# durtest4.net
KiCad netlist of a schematic drawn in EAGLE
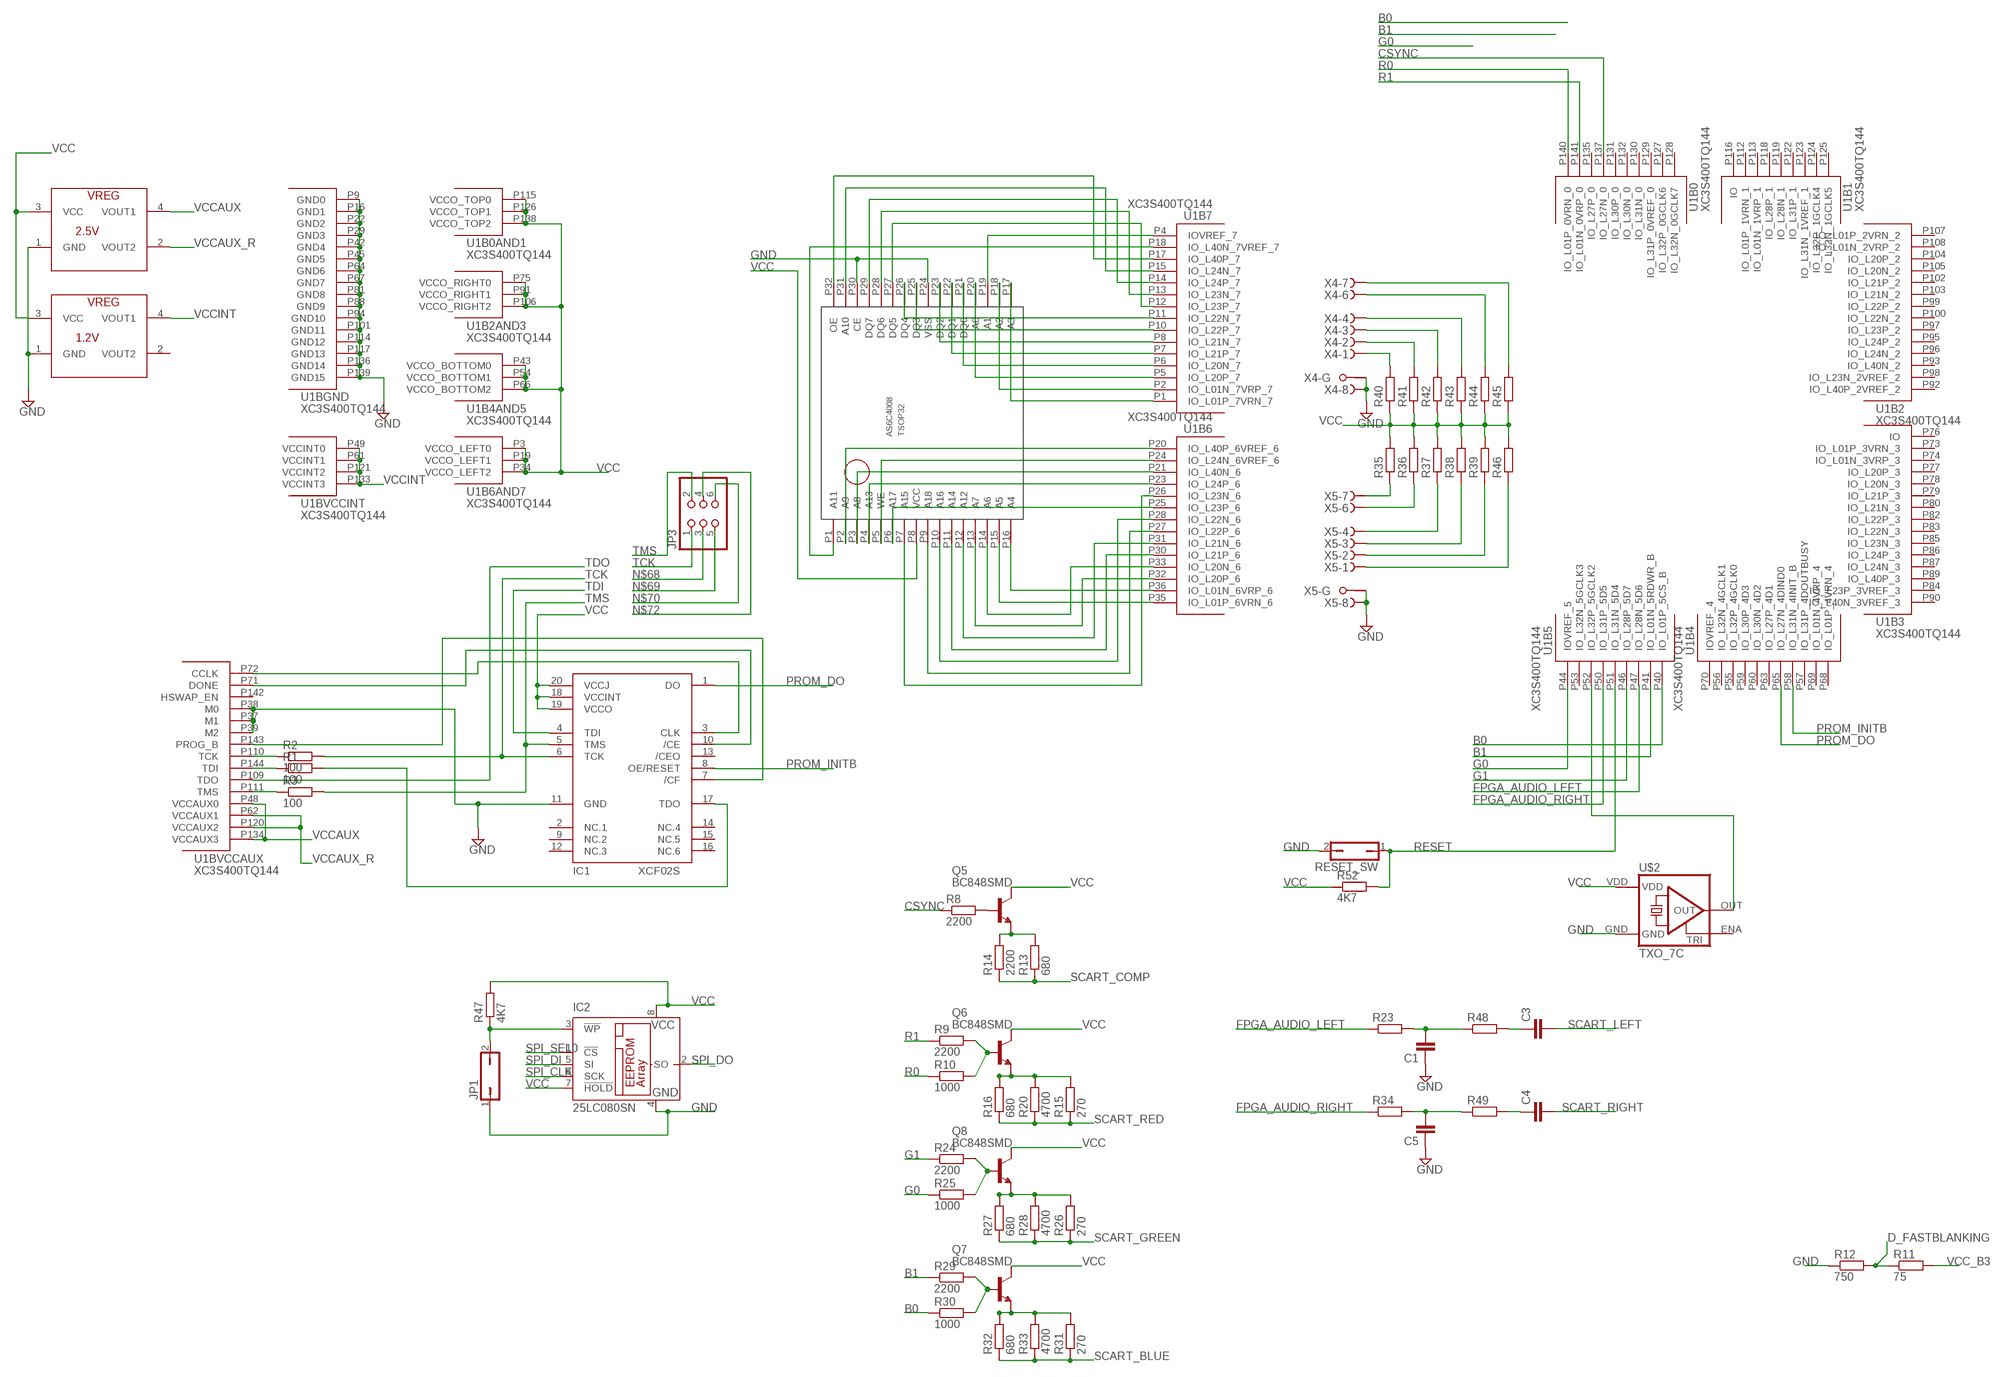
[diagram p0: schematic, sheet 1, part 1 of 2]
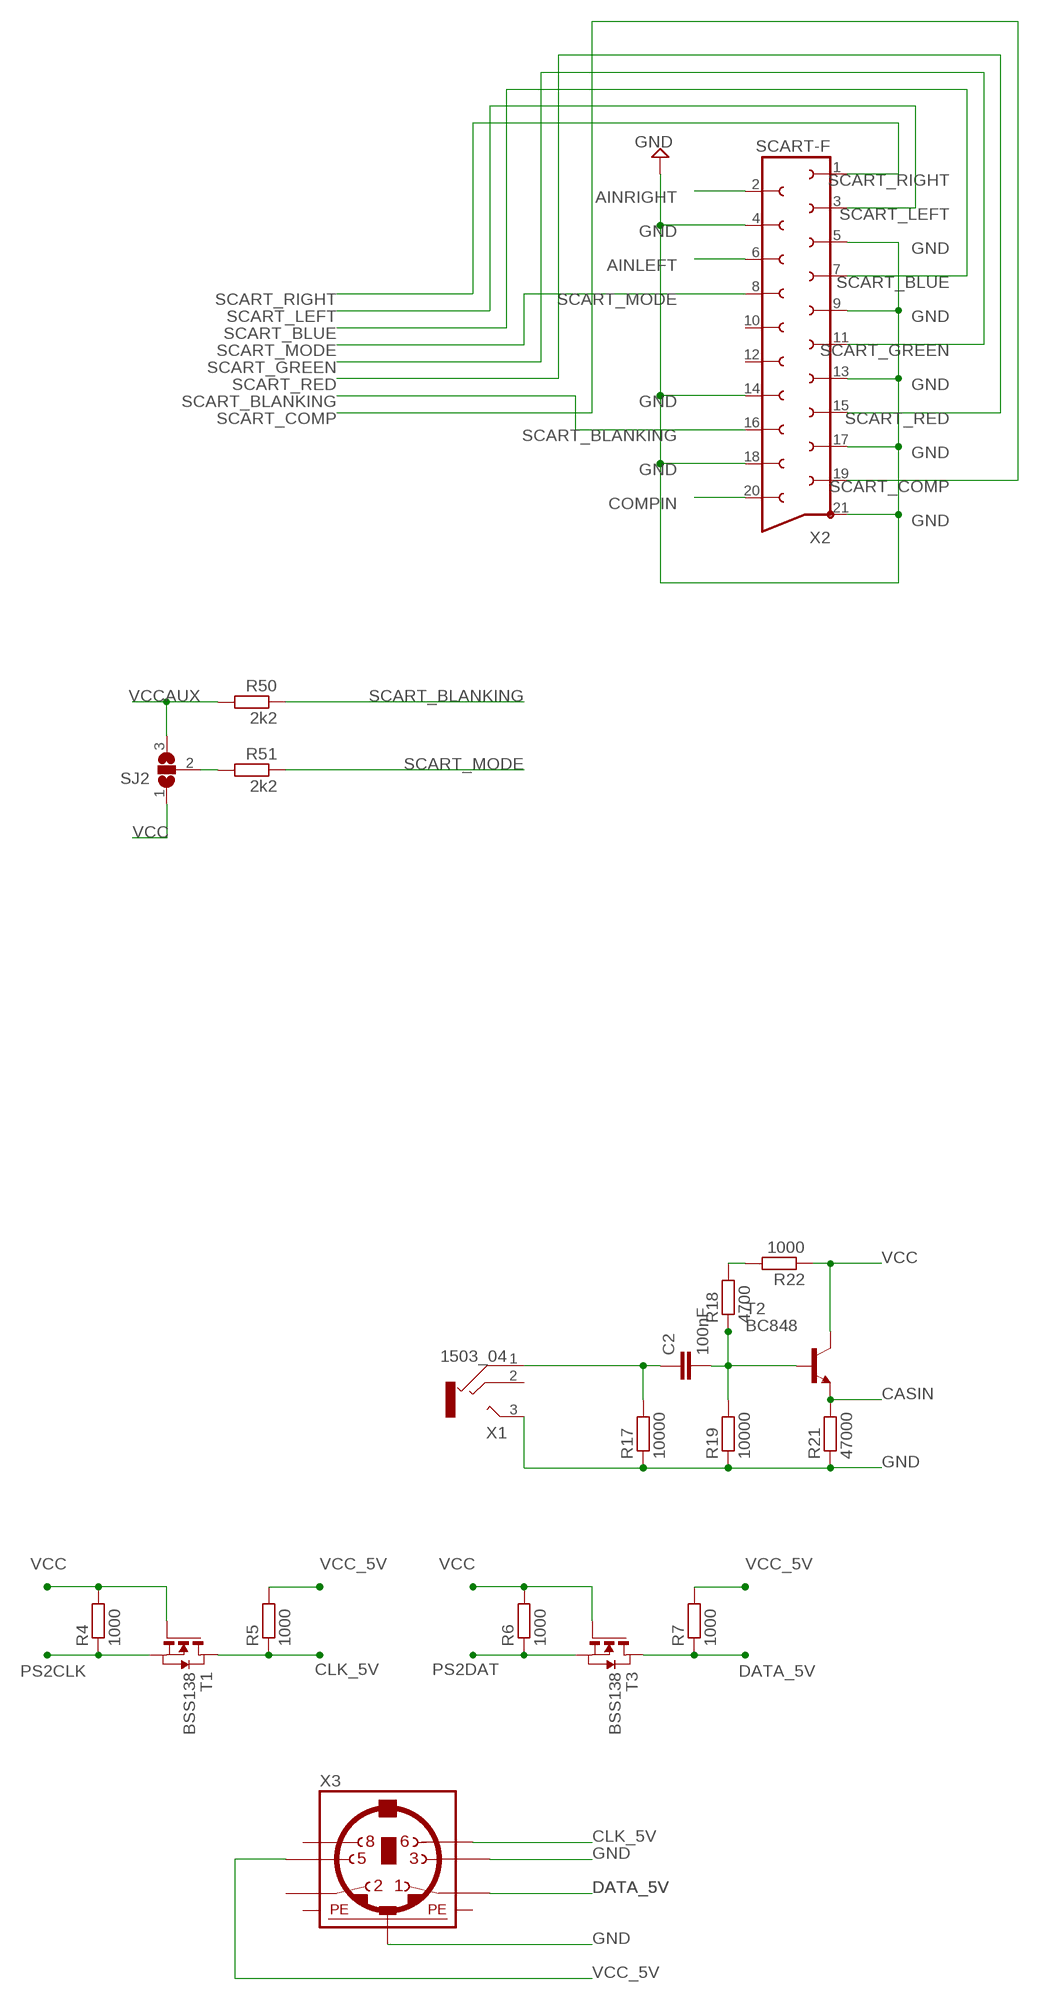
[diagram p1: schematic, sheet 1, part 2 of 2]

(export (version "E")
  (design (tool "Eeschema 10.0.6"))
  (components
    (comp (ref "C1")
      (value "C-EUC0603")
      (footprint "eagle-import:C0603")
      (libsource (lib "eagle-import") (part "C-EUC0603"))
    )
    (comp (ref "C2")
      (value "100nF")
      (footprint "eagle-import:C0603")
      (libsource (lib "eagle-import") (part "C-EUC0603"))
    )
    (comp (ref "C3")
      (value "C-EUC0603")
      (footprint "eagle-import:C0603")
      (libsource (lib "eagle-import") (part "C-EUC0603"))
    )
    (comp (ref "C4")
      (value "C-EUC0603")
      (footprint "eagle-import:C0603")
      (libsource (lib "eagle-import") (part "C-EUC0603"))
    )
    (comp (ref "C5")
      (value "C-EUC0603")
      (footprint "eagle-import:C0603")
      (libsource (lib "eagle-import") (part "C-EUC0603"))
    )
    (comp (ref "IC1")
      (value "XCF02S")
      (footprint "eagle-import:VO20")
      (libsource (lib "eagle-import") (part "XCF02S"))
    )
    (comp (ref "IC2")
      (value "25LC080SN")
      (footprint "eagle-import:SO-08")
      (fields (field (name "MF") "MICROCHIP") (field (name "MPN") "25LC080/SN"))
      (libsource (lib "eagle-import") (part "25SNLC080"))
    )
    (comp (ref "JP1")
      (value "JP1Q")
      (footprint "eagle-import:JP1")
      (libsource (lib "eagle-import") (part "JP1Q"))
    )
    (comp (ref "JP3")
      (value "PINHD-2X3")
      (footprint "eagle-import:2X03")
      (libsource (lib "eagle-import") (part "PINHD-2X3"))
    )
    (comp (ref "Q5")
      (value "BC848SMD")
      (footprint "eagle-import:SOT23")
      (libsource (lib "eagle-import") (part "BC848SMD"))
    )
    (comp (ref "Q6")
      (value "BC848SMD")
      (footprint "eagle-import:SOT23")
      (libsource (lib "eagle-import") (part "BC848SMD"))
    )
    (comp (ref "Q7")
      (value "BC848SMD")
      (footprint "eagle-import:SOT23")
      (libsource (lib "eagle-import") (part "BC848SMD"))
    )
    (comp (ref "Q8")
      (value "BC848SMD")
      (footprint "eagle-import:SOT23")
      (libsource (lib "eagle-import") (part "BC848SMD"))
    )
    (comp (ref "R1")
      (value "100")
      (footprint "eagle-import:R0805")
      (libsource (lib "eagle-import") (part "R-EU_R0805"))
    )
    (comp (ref "R2")
      (value "100")
      (footprint "eagle-import:R0805")
      (libsource (lib "eagle-import") (part "R-EU_R0805"))
    )
    (comp (ref "R3")
      (value "100")
      (footprint "eagle-import:R0805")
      (libsource (lib "eagle-import") (part "R-EU_R0805"))
    )
    (comp (ref "R4")
      (value "1000")
      (footprint "eagle-import:R0805")
      (libsource (lib "eagle-import") (part "R-EU_R0805"))
    )
    (comp (ref "R5")
      (value "1000")
      (footprint "eagle-import:R0805")
      (libsource (lib "eagle-import") (part "R-EU_R0805"))
    )
    (comp (ref "R6")
      (value "1000")
      (footprint "eagle-import:R0805")
      (libsource (lib "eagle-import") (part "R-EU_R0805"))
    )
    (comp (ref "R7")
      (value "1000")
      (footprint "eagle-import:R0805")
      (libsource (lib "eagle-import") (part "R-EU_R0805"))
    )
    (comp (ref "R8")
      (value "2200")
      (footprint "eagle-import:R0805")
      (libsource (lib "eagle-import") (part "R-EU_R0805"))
    )
    (comp (ref "R9")
      (value "2200")
      (footprint "eagle-import:R0805")
      (libsource (lib "eagle-import") (part "R-EU_R0805"))
    )
    (comp (ref "R10")
      (value "1000")
      (footprint "eagle-import:R0805")
      (libsource (lib "eagle-import") (part "R-EU_R0805"))
    )
    (comp (ref "R11")
      (value "75")
      (footprint "eagle-import:R0805")
      (libsource (lib "eagle-import") (part "R-EU_R0805"))
    )
    (comp (ref "R12")
      (value "750")
      (footprint "eagle-import:R0805")
      (libsource (lib "eagle-import") (part "R-EU_R0805"))
    )
    (comp (ref "R13")
      (value "680")
      (footprint "eagle-import:R0805")
      (libsource (lib "eagle-import") (part "R-EU_R0805"))
    )
    (comp (ref "R14")
      (value "2200")
      (footprint "eagle-import:R0805")
      (libsource (lib "eagle-import") (part "R-EU_R0805"))
    )
    (comp (ref "R15")
      (value "270")
      (footprint "eagle-import:R0805")
      (libsource (lib "eagle-import") (part "R-EU_R0805"))
    )
    (comp (ref "R16")
      (value "680")
      (footprint "eagle-import:R0805")
      (libsource (lib "eagle-import") (part "R-EU_R0805"))
    )
    (comp (ref "R17")
      (value "10000")
      (footprint "eagle-import:R0805")
      (libsource (lib "eagle-import") (part "R-EU_R0805"))
    )
    (comp (ref "R18")
      (value "4700")
      (footprint "eagle-import:R0805")
      (libsource (lib "eagle-import") (part "R-EU_R0805"))
    )
    (comp (ref "R19")
      (value "10000")
      (footprint "eagle-import:R0805")
      (libsource (lib "eagle-import") (part "R-EU_R0805"))
    )
    (comp (ref "R20")
      (value "4700")
      (footprint "eagle-import:R0805")
      (libsource (lib "eagle-import") (part "R-EU_R0805"))
    )
    (comp (ref "R21")
      (value "47000")
      (footprint "eagle-import:R0805")
      (libsource (lib "eagle-import") (part "R-EU_R0805"))
    )
    (comp (ref "R22")
      (value "1000")
      (footprint "eagle-import:R0805")
      (libsource (lib "eagle-import") (part "R-EU_R0805"))
    )
    (comp (ref "R23")
      (value "R-EU_M0805")
      (footprint "eagle-import:M0805")
      (libsource (lib "eagle-import") (part "resistor_R-EU_M0805"))
    )
    (comp (ref "R24")
      (value "2200")
      (footprint "eagle-import:R0805")
      (libsource (lib "eagle-import") (part "R-EU_R0805"))
    )
    (comp (ref "R25")
      (value "1000")
      (footprint "eagle-import:R0805")
      (libsource (lib "eagle-import") (part "R-EU_R0805"))
    )
    (comp (ref "R26")
      (value "270")
      (footprint "eagle-import:R0805")
      (libsource (lib "eagle-import") (part "R-EU_R0805"))
    )
    (comp (ref "R27")
      (value "680")
      (footprint "eagle-import:R0805")
      (libsource (lib "eagle-import") (part "R-EU_R0805"))
    )
    (comp (ref "R28")
      (value "4700")
      (footprint "eagle-import:R0805")
      (libsource (lib "eagle-import") (part "R-EU_R0805"))
    )
    (comp (ref "R29")
      (value "2200")
      (footprint "eagle-import:R0805")
      (libsource (lib "eagle-import") (part "R-EU_R0805"))
    )
    (comp (ref "R30")
      (value "1000")
      (footprint "eagle-import:R0805")
      (libsource (lib "eagle-import") (part "R-EU_R0805"))
    )
    (comp (ref "R31")
      (value "270")
      (footprint "eagle-import:R0805")
      (libsource (lib "eagle-import") (part "R-EU_R0805"))
    )
    (comp (ref "R32")
      (value "680")
      (footprint "eagle-import:R0805")
      (libsource (lib "eagle-import") (part "R-EU_R0805"))
    )
    (comp (ref "R33")
      (value "4700")
      (footprint "eagle-import:R0805")
      (libsource (lib "eagle-import") (part "R-EU_R0805"))
    )
    (comp (ref "R34")
      (value "R-EU_M0805")
      (footprint "eagle-import:M0805")
      (libsource (lib "eagle-import") (part "resistor_R-EU_M0805"))
    )
    (comp (ref "R35")
      (value "R-EU_M0805")
      (footprint "eagle-import:M0805")
      (libsource (lib "eagle-import") (part "resistor_R-EU_M0805"))
    )
    (comp (ref "R36")
      (value "R-EU_M0805")
      (footprint "eagle-import:M0805")
      (libsource (lib "eagle-import") (part "resistor_R-EU_M0805"))
    )
    (comp (ref "R37")
      (value "R-EU_M0805")
      (footprint "eagle-import:M0805")
      (libsource (lib "eagle-import") (part "resistor_R-EU_M0805"))
    )
    (comp (ref "R38")
      (value "R-EU_M0805")
      (footprint "eagle-import:M0805")
      (libsource (lib "eagle-import") (part "resistor_R-EU_M0805"))
    )
    (comp (ref "R39")
      (value "R-EU_M0805")
      (footprint "eagle-import:M0805")
      (libsource (lib "eagle-import") (part "resistor_R-EU_M0805"))
    )
    (comp (ref "R40")
      (value "R-EU_M0805")
      (footprint "eagle-import:M0805")
      (libsource (lib "eagle-import") (part "resistor_R-EU_M0805"))
    )
    (comp (ref "R41")
      (value "R-EU_M0805")
      (footprint "eagle-import:M0805")
      (libsource (lib "eagle-import") (part "resistor_R-EU_M0805"))
    )
    (comp (ref "R42")
      (value "R-EU_M0805")
      (footprint "eagle-import:M0805")
      (libsource (lib "eagle-import") (part "resistor_R-EU_M0805"))
    )
    (comp (ref "R43")
      (value "R-EU_M0805")
      (footprint "eagle-import:M0805")
      (libsource (lib "eagle-import") (part "resistor_R-EU_M0805"))
    )
    (comp (ref "R44")
      (value "R-EU_M0805")
      (footprint "eagle-import:M0805")
      (libsource (lib "eagle-import") (part "resistor_R-EU_M0805"))
    )
    (comp (ref "R45")
      (value "R-EU_M0805")
      (footprint "eagle-import:M0805")
      (libsource (lib "eagle-import") (part "resistor_R-EU_M0805"))
    )
    (comp (ref "R46")
      (value "R-EU_M0805")
      (footprint "eagle-import:M0805")
      (libsource (lib "eagle-import") (part "resistor_R-EU_M0805"))
    )
    (comp (ref "R47")
      (value "4K7")
      (footprint "eagle-import:R0805")
      (libsource (lib "eagle-import") (part "R-EU_R0805"))
    )
    (comp (ref "R48")
      (value "R-EU_M0805")
      (footprint "eagle-import:M0805")
      (libsource (lib "eagle-import") (part "resistor_R-EU_M0805"))
    )
    (comp (ref "R49")
      (value "R-EU_M0805")
      (footprint "eagle-import:M0805")
      (libsource (lib "eagle-import") (part "resistor_R-EU_M0805"))
    )
    (comp (ref "R50")
      (value "2k2")
      (footprint "eagle-import:M0805")
      (libsource (lib "eagle-import") (part "resistor_R-EU_M0805"))
    )
    (comp (ref "R51")
      (value "2k2")
      (footprint "eagle-import:M0805")
      (libsource (lib "eagle-import") (part "resistor_R-EU_M0805"))
    )
    (comp (ref "R52")
      (value "4K7")
      (footprint "eagle-import:M0805")
      (libsource (lib "eagle-import") (part "resistor_R-EU_M0805"))
    )
    (comp (ref "REG1.2")
      (value "1.2V")
      (footprint "eagle-import:SOT223")
      (libsource (lib "eagle-import") (part "NX1117"))
    )
    (comp (ref "REG2.5")
      (value "2.5V")
      (footprint "eagle-import:SOT223")
      (libsource (lib "eagle-import") (part "NX1117"))
    )
    (comp (ref "RESET_SW")
      (value "JP1Q")
      (footprint "eagle-import:JP1")
      (libsource (lib "eagle-import") (part "JP1Q"))
    )
    (comp (ref "SJ2")
      (value "SJ2W")
      (footprint "eagle-import:SJ_2")
      (libsource (lib "eagle-import") (part "SJ2W"))
    )
    (comp (ref "T1")
      (value "BSS138")
      (footprint "eagle-import:SOT-23")
      (libsource (lib "eagle-import") (part "NMOSSOT23"))
    )
    (comp (ref "T2")
      (value "BC848")
      (footprint "eagle-import:SOT23")
      (libsource (lib "eagle-import") (part "BC848"))
    )
    (comp (ref "T3")
      (value "BSS138")
      (footprint "eagle-import:SOT-23")
      (libsource (lib "eagle-import") (part "NMOSSOT23"))
    )
    (comp (ref "U$1")
      (value "AS6C4008")
      (footprint "eagle-import:TSOP32")
      (libsource (lib "eagle-import") (part "AS6C4008"))
    )
    (comp (ref "U$2")
      (value "TXO_7C")
      (footprint "eagle-import:OSC_7C")
      (libsource (lib "eagle-import") (part "TXO_7C"))
    )
    (comp (ref "U1")
      (value "XC3S400TQ144")
      (footprint "eagle-import:TQ144")
      (libsource (lib "eagle-import") (part "XC3S400TQ144"))
    )
    (comp (ref "X1")
      (value "1503_04")
      (footprint "eagle-import:1503_04")
      (libsource (lib "eagle-import") (part "1503_04"))
    )
    (comp (ref "X2")
      (value "SCART-F")
      (footprint "eagle-import:SCART-F")
      (libsource (lib "eagle-import") (part "SCART-F"))
    )
    (comp (ref "X3")
      (value "MINI_DIN_6")
      (footprint "eagle-import:M_DIN6")
      (libsource (lib "eagle-import") (part "MINI_DIN_6"))
    )
    (comp (ref "X4")
      (value "F09HPS")
      (footprint "eagle-import:F09HP")
      (libsource (lib "eagle-import") (part "F09HPS"))
    )
    (comp (ref "X5")
      (value "F09HPS")
      (footprint "eagle-import:F09HP")
      (libsource (lib "eagle-import") (part "F09HPS"))
    )
  )
  (nets
    (net (code "1") (name "/AINLEFT") (class "Default")
      (node (ref "X2") (pin "6") (pinfunction "6_6") (pintype "passive"))
    )
    (net (code "2") (name "/AINRIGHT") (class "Default")
      (node (ref "X2") (pin "2") (pinfunction "2_2") (pintype "passive"))
    )
    (net (code "3") (name "/B0") (class "Default")
      (node (ref "R30") (pin "1") (pinfunction "1_1") (pintype "passive"))
      (node (ref "U1") (pin "P40") (pinfunction "IO_L01P_5CS_B_P40") (pintype "bidirectional"))
    )
    (net (code "4") (name "/B1") (class "Default")
      (node (ref "R29") (pin "1") (pinfunction "1_1") (pintype "passive"))
      (node (ref "U1") (pin "P41") (pinfunction "IO_L01N_5RDWR_B_P41") (pintype "bidirectional"))
    )
    (net (code "5") (name "/CASIN") (class "Default")
      (node (ref "R21") (pin "2") (pinfunction "2_2") (pintype "passive"))
      (node (ref "T2") (pin "2") (pinfunction "E_2") (pintype "passive"))
    )
    (net (code "6") (name "/CLK_5V") (class "Default")
      (node (ref "R5") (pin "1") (pinfunction "1_1") (pintype "passive"))
      (node (ref "T1") (pin "1") (pinfunction "D_1") (pintype "passive"))
      (node (ref "X3") (pin "6") (pinfunction "6_6") (pintype "passive"))
    )
    (net (code "7") (name "/COMPIN") (class "Default")
      (node (ref "X2") (pin "20") (pinfunction "20_20") (pintype "passive"))
    )
    (net (code "8") (name "/CSYNC") (class "Default")
      (node (ref "R8") (pin "1") (pinfunction "1_1") (pintype "passive"))
      (node (ref "U1") (pin "P137") (pinfunction "IO_L27N_0_P137") (pintype "bidirectional"))
    )
    (net (code "9") (name "/DATA_5V") (class "Default")
      (node (ref "R7") (pin "1") (pinfunction "1_1") (pintype "passive"))
      (node (ref "T3") (pin "1") (pinfunction "D_1") (pintype "passive"))
      (node (ref "X3") (pin "1") (pinfunction "1_1") (pintype "passive"))
    )
    (net (code "10") (name "/D_FASTBLANKING") (class "Default")
      (node (ref "R11") (pin "1") (pinfunction "1_1") (pintype "passive"))
      (node (ref "R12") (pin "2") (pinfunction "2_2") (pintype "passive"))
    )
    (net (code "11") (name "/FPGA_AUDIO_LEFT") (class "Default")
      (node (ref "R23") (pin "1") (pinfunction "1_1") (pintype "passive"))
      (node (ref "U1") (pin "P47") (pinfunction "IO_L28N_5D6_P47") (pintype "bidirectional"))
    )
    (net (code "12") (name "/FPGA_AUDIO_RIGHT") (class "Default")
      (node (ref "R34") (pin "1") (pinfunction "1_1") (pintype "passive"))
      (node (ref "U1") (pin "P50") (pinfunction "IO_L31P_5D5_P50") (pintype "bidirectional"))
    )
    (net (code "13") (name "/G0") (class "Default")
      (node (ref "R25") (pin "1") (pinfunction "1_1") (pintype "passive"))
      (node (ref "U1") (pin "P44") (pinfunction "IOVREF_5_P44") (pintype "bidirectional"))
    )
    (net (code "14") (name "/G1") (class "Default")
      (node (ref "R24") (pin "1") (pinfunction "1_1") (pintype "passive"))
      (node (ref "U1") (pin "P46") (pinfunction "IO_L28P_5D7_P46") (pintype "bidirectional"))
    )
    (net (code "15") (name "/N$68") (class "Default")
      (node (ref "JP3") (pin "3") (pinfunction "3_3") (pintype "passive"))
    )
    (net (code "16") (name "/N$69") (class "Default")
      (node (ref "JP3") (pin "5") (pinfunction "5_5") (pintype "passive"))
    )
    (net (code "17") (name "/N$70") (class "Default")
      (node (ref "JP3") (pin "6") (pinfunction "6_6") (pintype "passive"))
    )
    (net (code "18") (name "/N$72") (class "Default")
      (node (ref "JP3") (pin "4") (pinfunction "4_4") (pintype "passive"))
    )
    (net (code "19") (name "/PE1") (class "Default")
      (node (ref "X3") (pin "SH1") (pinfunction "PE1_SH1") (pintype "power_in"))
    )
    (net (code "20") (name "/PE3") (class "Default")
      (node (ref "X3") (pin "SH3") (pinfunction "PE3_SH3") (pintype "power_in"))
    )
    (net (code "21") (name "/PROM_DO") (class "Default")
      (node (ref "IC1") (pin "1") (pinfunction "DO_1") (pintype "bidirectional"))
      (node (ref "U1") (pin "P65") (pinfunction "IO_L27N_4DIND0_P65") (pintype "bidirectional"))
    )
    (net (code "22") (name "/PROM_INITB") (class "Default")
      (node (ref "IC1") (pin "8") (pinfunction "OE/RESET_8") (pintype "bidirectional"))
      (node (ref "U1") (pin "P58") (pinfunction "IO_L31N_4INIT_B_P58") (pintype "bidirectional"))
    )
    (net (code "23") (name "/PS2CLK") (class "Default")
      (node (ref "R4") (pin "1") (pinfunction "1_1") (pintype "passive"))
      (node (ref "T1") (pin "2") (pinfunction "S_2") (pintype "passive"))
    )
    (net (code "24") (name "/PS2DAT") (class "Default")
      (node (ref "R6") (pin "1") (pinfunction "1_1") (pintype "passive"))
      (node (ref "T3") (pin "2") (pinfunction "S_2") (pintype "passive"))
    )
    (net (code "25") (name "/R0") (class "Default")
      (node (ref "R10") (pin "1") (pinfunction "1_1") (pintype "passive"))
      (node (ref "U1") (pin "P140") (pinfunction "IO_L01P_0VRN_0_P140") (pintype "bidirectional"))
    )
    (net (code "26") (name "/R1") (class "Default")
      (node (ref "R9") (pin "1") (pinfunction "1_1") (pintype "passive"))
      (node (ref "U1") (pin "P141") (pinfunction "IO_L01N_0VRP_0_P141") (pintype "bidirectional"))
    )
    (net (code "27") (name "/RESET") (class "Default")
      (node (ref "R52") (pin "2") (pinfunction "2_2") (pintype "passive"))
      (node (ref "RESET_SW") (pin "1") (pinfunction "1_1") (pintype "passive"))
      (node (ref "U1") (pin "P51") (pinfunction "IO_L31N_5D4_P51") (pintype "bidirectional"))
    )
    (net (code "28") (name "/SCART_BLANKING") (class "Default")
      (node (ref "R50") (pin "1") (pinfunction "1_1") (pintype "passive"))
      (node (ref "X2") (pin "16") (pinfunction "16_16") (pintype "passive"))
    )
    (net (code "29") (name "/SCART_BLUE") (class "Default")
      (node (ref "R31") (pin "1") (pinfunction "1_1") (pintype "passive"))
      (node (ref "R32") (pin "1") (pinfunction "1_1") (pintype "passive"))
      (node (ref "R33") (pin "1") (pinfunction "1_1") (pintype "passive"))
      (node (ref "X2") (pin "7") (pinfunction "7_7") (pintype "passive"))
    )
    (net (code "30") (name "/SCART_COMP") (class "Default")
      (node (ref "R13") (pin "1") (pinfunction "1_1") (pintype "passive"))
      (node (ref "R14") (pin "1") (pinfunction "1_1") (pintype "passive"))
      (node (ref "X2") (pin "19") (pinfunction "19_19") (pintype "passive"))
    )
    (net (code "31") (name "/SCART_GREEN") (class "Default")
      (node (ref "R26") (pin "1") (pinfunction "1_1") (pintype "passive"))
      (node (ref "R27") (pin "1") (pinfunction "1_1") (pintype "passive"))
      (node (ref "R28") (pin "1") (pinfunction "1_1") (pintype "passive"))
      (node (ref "X2") (pin "11") (pinfunction "11_11") (pintype "passive"))
    )
    (net (code "32") (name "/SCART_LEFT") (class "Default")
      (node (ref "C3") (pin "2") (pinfunction "2_2") (pintype "passive"))
      (node (ref "X2") (pin "3") (pinfunction "3_3") (pintype "passive"))
    )
    (net (code "33") (name "/SCART_MODE") (class "Default")
      (node (ref "R51") (pin "1") (pinfunction "1_1") (pintype "passive"))
      (node (ref "X2") (pin "8") (pinfunction "8_8") (pintype "passive"))
    )
    (net (code "34") (name "/SCART_RED") (class "Default")
      (node (ref "R15") (pin "1") (pinfunction "1_1") (pintype "passive"))
      (node (ref "R16") (pin "1") (pinfunction "1_1") (pintype "passive"))
      (node (ref "R20") (pin "1") (pinfunction "1_1") (pintype "passive"))
      (node (ref "X2") (pin "15") (pinfunction "15_15") (pintype "passive"))
    )
    (net (code "35") (name "/SCART_RIGHT") (class "Default")
      (node (ref "C4") (pin "2") (pinfunction "2_2") (pintype "passive"))
      (node (ref "X2") (pin "1") (pinfunction "1_1") (pintype "passive"))
    )
    (net (code "36") (name "/SPI_CLK") (class "Default")
      (node (ref "IC2") (pin "6") (pinfunction "SCK_6") (pintype "input"))
    )
    (net (code "37") (name "/SPI_DI") (class "Default")
      (node (ref "IC2") (pin "5") (pinfunction "SI_5") (pintype "input"))
    )
    (net (code "38") (name "/SPI_DO") (class "Default")
      (node (ref "IC2") (pin "2") (pinfunction "SO_2") (pintype "bidirectional"))
    )
    (net (code "39") (name "/SPI_SEL0") (class "Default")
      (node (ref "IC2") (pin "1") (pinfunction "~{CS}_1") (pintype "input"))
    )
    (net (code "40") (name "/TCK") (class "Default")
      (node (ref "IC1") (pin "6") (pinfunction "TCK_6") (pintype "bidirectional"))
      (node (ref "JP3") (pin "1") (pinfunction "1_1") (pintype "passive"))
      (node (ref "R2") (pin "2") (pinfunction "2_2") (pintype "passive"))
    )
    (net (code "41") (name "/TDI") (class "Default")
      (node (ref "IC1") (pin "4") (pinfunction "TDI_4") (pintype "bidirectional"))
    )
    (net (code "42") (name "/TDO") (class "Default")
      (node (ref "U1") (pin "P109") (pinfunction "TDO_P109") (pintype "bidirectional"))
    )
    (net (code "43") (name "/TMS") (class "Default")
      (node (ref "IC1") (pin "5") (pinfunction "TMS_5") (pintype "bidirectional"))
      (node (ref "JP3") (pin "2") (pinfunction "2_2") (pintype "passive"))
      (node (ref "R3") (pin "2") (pinfunction "2_2") (pintype "passive"))
    )
    (net (code "44") (name "/VCC") (class "Default")
      (node (ref "IC1") (pin "18") (pinfunction "VCCINT_18") (pintype "bidirectional"))
      (node (ref "IC1") (pin "19") (pinfunction "VCCO_19") (pintype "bidirectional"))
      (node (ref "IC1") (pin "20") (pinfunction "VCCJ_20") (pintype "bidirectional"))
      (node (ref "IC2") (pin "7") (pinfunction "~{HOLD}_7") (pintype "input"))
      (node (ref "IC2") (pin "8") (pinfunction "VCC_8") (pintype "power_in"))
      (node (ref "Q5") (pin "3") (pinfunction "C_3") (pintype "passive"))
      (node (ref "Q6") (pin "3") (pinfunction "C_3") (pintype "passive"))
      (node (ref "Q7") (pin "3") (pinfunction "C_3") (pintype "passive"))
      (node (ref "Q8") (pin "3") (pinfunction "C_3") (pintype "passive"))
      (node (ref "R22") (pin "1") (pinfunction "1_1") (pintype "passive"))
      (node (ref "R35") (pin "2") (pinfunction "2_2") (pintype "passive"))
      (node (ref "R36") (pin "2") (pinfunction "2_2") (pintype "passive"))
      (node (ref "R37") (pin "2") (pinfunction "2_2") (pintype "passive"))
      (node (ref "R38") (pin "2") (pinfunction "2_2") (pintype "passive"))
      (node (ref "R39") (pin "2") (pinfunction "2_2") (pintype "passive"))
      (node (ref "R4") (pin "2") (pinfunction "2_2") (pintype "passive"))
      (node (ref "R40") (pin "1") (pinfunction "1_1") (pintype "passive"))
      (node (ref "R41") (pin "1") (pinfunction "1_1") (pintype "passive"))
      (node (ref "R42") (pin "1") (pinfunction "1_1") (pintype "passive"))
      (node (ref "R43") (pin "1") (pinfunction "1_1") (pintype "passive"))
      (node (ref "R44") (pin "1") (pinfunction "1_1") (pintype "passive"))
      (node (ref "R45") (pin "1") (pinfunction "1_1") (pintype "passive"))
      (node (ref "R46") (pin "2") (pinfunction "2_2") (pintype "passive"))
      (node (ref "R47") (pin "2") (pinfunction "2_2") (pintype "passive"))
      (node (ref "R52") (pin "1") (pinfunction "1_1") (pintype "passive"))
      (node (ref "R6") (pin "2") (pinfunction "2_2") (pintype "passive"))
      (node (ref "REG1.2") (pin "3") (pinfunction "VCC_3") (pintype "bidirectional"))
      (node (ref "REG2.5") (pin "3") (pinfunction "VCC_3") (pintype "bidirectional"))
      (node (ref "SJ2") (pin "1") (pinfunction "1_1") (pintype "passive"))
      (node (ref "T1") (pin "3") (pinfunction "G_3") (pintype "passive"))
      (node (ref "T2") (pin "3") (pinfunction "C_3") (pintype "passive"))
      (node (ref "T3") (pin "3") (pinfunction "G_3") (pintype "passive"))
      (node (ref "U$1") (pin "P8") (pinfunction "VCC_P8") (pintype "bidirectional"))
      (node (ref "U$2") (pin "VDD") (pinfunction "VDD_VDD") (pintype "power_in"))
      (node (ref "U1") (pin "P106") (pinfunction "VCCO_RIGHT2_P106") (pintype "passive"))
      (node (ref "U1") (pin "P115") (pinfunction "VCCO_TOP0_P115") (pintype "passive"))
      (node (ref "U1") (pin "P126") (pinfunction "VCCO_TOP1_P126") (pintype "passive"))
      (node (ref "U1") (pin "P138") (pinfunction "VCCO_TOP2_P138") (pintype "passive"))
      (node (ref "U1") (pin "P19") (pinfunction "VCCO_LEFT1_P19") (pintype "passive"))
      (node (ref "U1") (pin "P3") (pinfunction "VCCO_LEFT0_P3") (pintype "passive"))
      (node (ref "U1") (pin "P34") (pinfunction "VCCO_LEFT2_P34") (pintype "passive"))
      (node (ref "U1") (pin "P43") (pinfunction "VCCO_BOTTOM0_P43") (pintype "passive"))
      (node (ref "U1") (pin "P54") (pinfunction "VCCO_BOTTOM1_P54") (pintype "passive"))
      (node (ref "U1") (pin "P66") (pinfunction "VCCO_BOTTOM2_P66") (pintype "passive"))
      (node (ref "U1") (pin "P75") (pinfunction "VCCO_RIGHT0_P75") (pintype "passive"))
      (node (ref "U1") (pin "P91") (pinfunction "VCCO_RIGHT1_P91") (pintype "passive"))
    )
    (net (code "45") (name "/VCCAUX") (class "Default")
      (node (ref "R50") (pin "2") (pinfunction "2_2") (pintype "passive"))
      (node (ref "REG2.5") (pin "4") (pinfunction "VOUT1_4") (pintype "bidirectional"))
      (node (ref "SJ2") (pin "3") (pinfunction "3_3") (pintype "passive"))
      (node (ref "U1") (pin "P134") (pinfunction "VCCAUX3_P134") (pintype "passive"))
      (node (ref "U1") (pin "P48") (pinfunction "VCCAUX0_P48") (pintype "passive"))
    )
    (net (code "46") (name "/VCCAUX_R") (class "Default")
      (node (ref "REG2.5") (pin "2") (pinfunction "VOUT2_2") (pintype "bidirectional"))
      (node (ref "U1") (pin "P120") (pinfunction "VCCAUX2_P120") (pintype "passive"))
      (node (ref "U1") (pin "P62") (pinfunction "VCCAUX1_P62") (pintype "passive"))
    )
    (net (code "47") (name "/VCCINT") (class "Default")
      (node (ref "REG1.2") (pin "4") (pinfunction "VOUT1_4") (pintype "bidirectional"))
      (node (ref "U1") (pin "P121") (pinfunction "VCCINT2_P121") (pintype "passive"))
      (node (ref "U1") (pin "P133") (pinfunction "VCCINT3_P133") (pintype "passive"))
      (node (ref "U1") (pin "P49") (pinfunction "VCCINT0_P49") (pintype "passive"))
      (node (ref "U1") (pin "P61") (pinfunction "VCCINT1_P61") (pintype "passive"))
    )
    (net (code "48") (name "/VCC_5V") (class "Default")
      (node (ref "R5") (pin "2") (pinfunction "2_2") (pintype "passive"))
      (node (ref "R7") (pin "2") (pinfunction "2_2") (pintype "passive"))
      (node (ref "X3") (pin "5") (pinfunction "5_5") (pintype "passive"))
    )
    (net (code "49") (name "/VCC_B3") (class "Default")
      (node (ref "R11") (pin "2") (pinfunction "2_2") (pintype "passive"))
    )
    (net (code "50") (name "GND") (class "Default")
      (node (ref "C1") (pin "1") (pinfunction "1_1") (pintype "passive"))
      (node (ref "C5") (pin "1") (pinfunction "1_1") (pintype "passive"))
      (node (ref "IC1") (pin "11") (pinfunction "GND_11") (pintype "bidirectional"))
      (node (ref "IC2") (pin "4") (pinfunction "GND_4") (pintype "power_in"))
      (node (ref "JP1") (pin "1") (pinfunction "1_1") (pintype "passive"))
      (node (ref "R12") (pin "1") (pinfunction "1_1") (pintype "passive"))
      (node (ref "R17") (pin "1") (pinfunction "1_1") (pintype "passive"))
      (node (ref "R19") (pin "1") (pinfunction "1_1") (pintype "passive"))
      (node (ref "R21") (pin "1") (pinfunction "1_1") (pintype "passive"))
      (node (ref "REG1.2") (pin "1") (pinfunction "GND_1") (pintype "bidirectional"))
      (node (ref "REG2.5") (pin "1") (pinfunction "GND_1") (pintype "bidirectional"))
      (node (ref "RESET_SW") (pin "2") (pinfunction "2_2") (pintype "passive"))
      (node (ref "U$1") (pin "P24") (pinfunction "VSS_P24") (pintype "bidirectional"))
      (node (ref "U$1") (pin "P30") (pinfunction "CE_P30") (pintype "bidirectional"))
      (node (ref "U$2") (pin "GND") (pinfunction "GND_GND") (pintype "power_in"))
      (node (ref "U1") (pin "P101") (pinfunction "GND11_P101") (pintype "passive"))
      (node (ref "U1") (pin "P114") (pinfunction "GND12_P114") (pintype "passive"))
      (node (ref "U1") (pin "P117") (pinfunction "GND13_P117") (pintype "passive"))
      (node (ref "U1") (pin "P136") (pinfunction "GND14_P136") (pintype "passive"))
      (node (ref "U1") (pin "P139") (pinfunction "GND15_P139") (pintype "passive"))
      (node (ref "U1") (pin "P16") (pinfunction "GND1_P16") (pintype "passive"))
      (node (ref "U1") (pin "P22") (pinfunction "GND2_P22") (pintype "passive"))
      (node (ref "U1") (pin "P29") (pinfunction "GND3_P29") (pintype "passive"))
      (node (ref "U1") (pin "P37") (pinfunction "M1_P37") (pintype "bidirectional"))
      (node (ref "U1") (pin "P38") (pinfunction "M0_P38") (pintype "bidirectional"))
      (node (ref "U1") (pin "P39") (pinfunction "M2_P39") (pintype "bidirectional"))
      (node (ref "U1") (pin "P42") (pinfunction "GND4_P42") (pintype "passive"))
      (node (ref "U1") (pin "P45") (pinfunction "GND5_P45") (pintype "passive"))
      (node (ref "U1") (pin "P64") (pinfunction "GND6_P64") (pintype "passive"))
      (node (ref "U1") (pin "P67") (pinfunction "GND7_P67") (pintype "passive"))
      (node (ref "U1") (pin "P81") (pinfunction "GND8_P81") (pintype "passive"))
      (node (ref "U1") (pin "P88") (pinfunction "GND9_P88") (pintype "passive"))
      (node (ref "U1") (pin "P9") (pinfunction "GND0_P9") (pintype "passive"))
      (node (ref "U1") (pin "P94") (pinfunction "GND10_P94") (pintype "passive"))
      (node (ref "X1") (pin "3") (pinfunction "2_3") (pintype "passive"))
      (node (ref "X2") (pin "13") (pinfunction "13_13") (pintype "passive"))
      (node (ref "X2") (pin "14") (pinfunction "14_14") (pintype "passive"))
      (node (ref "X2") (pin "17") (pinfunction "17_17") (pintype "passive"))
      (node (ref "X2") (pin "18") (pinfunction "18_18") (pintype "passive"))
      (node (ref "X2") (pin "21") (pinfunction "21_21") (pintype "passive"))
      (node (ref "X2") (pin "4") (pinfunction "4_4") (pintype "passive"))
      (node (ref "X2") (pin "5") (pinfunction "5_5") (pintype "passive"))
      (node (ref "X2") (pin "9") (pinfunction "9_9") (pintype "passive"))
      (node (ref "X3") (pin "3") (pinfunction "3_3") (pintype "passive"))
      (node (ref "X3") (pin "SH2") (pinfunction "PE2_SH2") (pintype "power_in"))
      (node (ref "X4") (pin "8") (pinfunction "F_8") (pintype "passive"))
      (node (ref "X4") (pin "G1") (pinfunction "G1_G1") (pintype "passive"))
      (node (ref "X5") (pin "8") (pinfunction "F_8") (pintype "passive"))
      (node (ref "X5") (pin "G1") (pinfunction "G1_G1") (pintype "passive"))
    )
    (net (code "51") (name "Net-(C1-Pad2)") (class "Default")
      (node (ref "C1") (pin "2") (pinfunction "2_2") (pintype "passive"))
      (node (ref "R23") (pin "2") (pinfunction "2_2") (pintype "passive"))
      (node (ref "R48") (pin "1") (pinfunction "1_1") (pintype "passive"))
    )
    (net (code "52") (name "Net-(C2-Pad1)") (class "Default")
      (node (ref "C2") (pin "1") (pinfunction "1_1") (pintype "passive"))
      (node (ref "R17") (pin "2") (pinfunction "2_2") (pintype "passive"))
      (node (ref "X1") (pin "1") (pinfunction "1_1") (pintype "passive"))
    )
    (net (code "53") (name "Net-(C3-Pad1)") (class "Default")
      (node (ref "C3") (pin "1") (pinfunction "1_1") (pintype "passive"))
      (node (ref "R48") (pin "2") (pinfunction "2_2") (pintype "passive"))
    )
    (net (code "54") (name "Net-(C4-Pad1)") (class "Default")
      (node (ref "C4") (pin "1") (pinfunction "1_1") (pintype "passive"))
      (node (ref "R49") (pin "2") (pinfunction "2_2") (pintype "passive"))
    )
    (net (code "55") (name "Net-(C5-Pad2)") (class "Default")
      (node (ref "C5") (pin "2") (pinfunction "2_2") (pintype "passive"))
      (node (ref "R34") (pin "2") (pinfunction "2_2") (pintype "passive"))
      (node (ref "R49") (pin "1") (pinfunction "1_1") (pintype "passive"))
    )
    (net (code "56") (name "Net-(IC1-CLK)") (class "Default")
      (node (ref "IC1") (pin "3") (pinfunction "CLK_3") (pintype "bidirectional"))
      (node (ref "U1") (pin "P72") (pinfunction "CCLK_P72") (pintype "bidirectional"))
    )
    (net (code "57") (name "Net-(IC1-TDO)") (class "Default")
      (node (ref "IC1") (pin "17") (pinfunction "TDO_17") (pintype "bidirectional"))
      (node (ref "R1") (pin "2") (pinfunction "2_2") (pintype "passive"))
    )
    (net (code "58") (name "Net-(IC1-{slash}CE)") (class "Default")
      (node (ref "IC1") (pin "10") (pinfunction "/CE_10") (pintype "bidirectional"))
      (node (ref "U1") (pin "P71") (pinfunction "DONE_P71") (pintype "bidirectional"))
    )
    (net (code "59") (name "Net-(IC1-{slash}CF)") (class "Default")
      (node (ref "IC1") (pin "7") (pinfunction "/CF_7") (pintype "bidirectional"))
      (node (ref "U1") (pin "P143") (pinfunction "PROG_B_P143") (pintype "bidirectional"))
    )
    (net (code "60") (name "Net-(IC2-~{WP})") (class "Default")
      (node (ref "IC2") (pin "3") (pinfunction "~{WP}_3") (pintype "input"))
      (node (ref "JP1") (pin "2") (pinfunction "2_2") (pintype "passive"))
      (node (ref "R47") (pin "1") (pinfunction "1_1") (pintype "passive"))
    )
    (net (code "61") (name "Net-(Q5-B)") (class "Default")
      (node (ref "Q5") (pin "1") (pinfunction "B_1") (pintype "passive"))
      (node (ref "R8") (pin "2") (pinfunction "2_2") (pintype "passive"))
    )
    (net (code "62") (name "Net-(Q5-E)") (class "Default")
      (node (ref "Q5") (pin "2") (pinfunction "E_2") (pintype "passive"))
      (node (ref "R13") (pin "2") (pinfunction "2_2") (pintype "passive"))
      (node (ref "R14") (pin "2") (pinfunction "2_2") (pintype "passive"))
    )
    (net (code "63") (name "Net-(Q6-B)") (class "Default")
      (node (ref "Q6") (pin "1") (pinfunction "B_1") (pintype "passive"))
      (node (ref "R10") (pin "2") (pinfunction "2_2") (pintype "passive"))
      (node (ref "R9") (pin "2") (pinfunction "2_2") (pintype "passive"))
    )
    (net (code "64") (name "Net-(Q6-E)") (class "Default")
      (node (ref "Q6") (pin "2") (pinfunction "E_2") (pintype "passive"))
      (node (ref "R15") (pin "2") (pinfunction "2_2") (pintype "passive"))
      (node (ref "R16") (pin "2") (pinfunction "2_2") (pintype "passive"))
      (node (ref "R20") (pin "2") (pinfunction "2_2") (pintype "passive"))
    )
    (net (code "65") (name "Net-(Q7-B)") (class "Default")
      (node (ref "Q7") (pin "1") (pinfunction "B_1") (pintype "passive"))
      (node (ref "R29") (pin "2") (pinfunction "2_2") (pintype "passive"))
      (node (ref "R30") (pin "2") (pinfunction "2_2") (pintype "passive"))
    )
    (net (code "66") (name "Net-(Q7-E)") (class "Default")
      (node (ref "Q7") (pin "2") (pinfunction "E_2") (pintype "passive"))
      (node (ref "R31") (pin "2") (pinfunction "2_2") (pintype "passive"))
      (node (ref "R32") (pin "2") (pinfunction "2_2") (pintype "passive"))
      (node (ref "R33") (pin "2") (pinfunction "2_2") (pintype "passive"))
    )
    (net (code "67") (name "Net-(Q8-B)") (class "Default")
      (node (ref "Q8") (pin "1") (pinfunction "B_1") (pintype "passive"))
      (node (ref "R24") (pin "2") (pinfunction "2_2") (pintype "passive"))
      (node (ref "R25") (pin "2") (pinfunction "2_2") (pintype "passive"))
    )
    (net (code "68") (name "Net-(Q8-E)") (class "Default")
      (node (ref "Q8") (pin "2") (pinfunction "E_2") (pintype "passive"))
      (node (ref "R26") (pin "2") (pinfunction "2_2") (pintype "passive"))
      (node (ref "R27") (pin "2") (pinfunction "2_2") (pintype "passive"))
      (node (ref "R28") (pin "2") (pinfunction "2_2") (pintype "passive"))
    )
    (net (code "69") (name "Net-(R18-Pad2)") (class "Default")
      (node (ref "R18") (pin "2") (pinfunction "2_2") (pintype "passive"))
      (node (ref "R22") (pin "2") (pinfunction "2_2") (pintype "passive"))
    )
    (net (code "70") (name "Net-(R51-Pad2)") (class "Default")
      (node (ref "R51") (pin "2") (pinfunction "2_2") (pintype "passive"))
      (node (ref "SJ2") (pin "2") (pinfunction "2_2") (pintype "passive"))
    )
    (net (code "71") (name "Net-(T2-B)") (class "Default")
      (node (ref "C2") (pin "2") (pinfunction "2_2") (pintype "passive"))
      (node (ref "R18") (pin "1") (pinfunction "1_1") (pintype "passive"))
      (node (ref "R19") (pin "2") (pinfunction "2_2") (pintype "passive"))
      (node (ref "T2") (pin "1") (pinfunction "B_1") (pintype "passive"))
    )
    (net (code "72") (name "Net-(U$1-A0)") (class "Default")
      (node (ref "U$1") (pin "P20") (pinfunction "A0_P20") (pintype "bidirectional"))
      (node (ref "U1") (pin "P5") (pinfunction "IO_L20P_7_P5") (pintype "bidirectional"))
    )
    (net (code "73") (name "Net-(U$1-A1)") (class "Default")
      (node (ref "U$1") (pin "P19") (pinfunction "A1_P19") (pintype "bidirectional"))
      (node (ref "U1") (pin "P4") (pinfunction "IOVREF_7_P4") (pintype "bidirectional"))
    )
    (net (code "74") (name "Net-(U$1-A2)") (class "Default")
      (node (ref "U$1") (pin "P18") (pinfunction "A2_P18") (pintype "bidirectional"))
      (node (ref "U1") (pin "P2") (pinfunction "IO_L01N_7VRP_7_P2") (pintype "bidirectional"))
    )
    (net (code "75") (name "Net-(U$1-A3)") (class "Default")
      (node (ref "U$1") (pin "P17") (pinfunction "A3_P17") (pintype "bidirectional"))
      (node (ref "U1") (pin "P1") (pinfunction "IO_L01P_7VRN_7_P1") (pintype "bidirectional"))
    )
    (net (code "76") (name "Net-(U$1-A4)") (class "Default")
      (node (ref "U$1") (pin "P16") (pinfunction "A4_P16") (pintype "bidirectional"))
      (node (ref "U1") (pin "P36") (pinfunction "IO_L01N_6VRP_6_P36") (pintype "bidirectional"))
    )
    (net (code "77") (name "Net-(U$1-A5)") (class "Default")
      (node (ref "U$1") (pin "P15") (pinfunction "A5_P15") (pintype "bidirectional"))
      (node (ref "U1") (pin "P35") (pinfunction "IO_L01P_6VRN_6_P35") (pintype "bidirectional"))
    )
    (net (code "78") (name "Net-(U$1-A6)") (class "Default")
      (node (ref "U$1") (pin "P14") (pinfunction "A6_P14") (pintype "bidirectional"))
      (node (ref "U1") (pin "P33") (pinfunction "IO_L20N_6_P33") (pintype "bidirectional"))
    )
    (net (code "79") (name "Net-(U$1-A7)") (class "Default")
      (node (ref "U$1") (pin "P13") (pinfunction "A7_P13") (pintype "bidirectional"))
      (node (ref "U1") (pin "P32") (pinfunction "IO_L20P_6_P32") (pintype "bidirectional"))
    )
    (net (code "80") (name "Net-(U$1-A8)") (class "Default")
      (node (ref "U$1") (pin "P3") (pinfunction "A8_P3") (pintype "bidirectional"))
      (node (ref "U1") (pin "P21") (pinfunction "IO_L40N_6_P21") (pintype "bidirectional"))
    )
    (net (code "81") (name "Net-(U$1-A9)") (class "Default")
      (node (ref "U$1") (pin "P2") (pinfunction "A9_P2") (pintype "bidirectional"))
      (node (ref "U1") (pin "P20") (pinfunction "IO_L40P_6VREF_6_P20") (pintype "bidirectional"))
    )
    (net (code "82") (name "Net-(U$1-A10)") (class "Default")
      (node (ref "U$1") (pin "P31") (pinfunction "A10_P31") (pintype "bidirectional"))
      (node (ref "U1") (pin "P15") (pinfunction "IO_L24N_7_P15") (pintype "bidirectional"))
    )
    (net (code "83") (name "Net-(U$1-A11)") (class "Default")
      (node (ref "U$1") (pin "P1") (pinfunction "A11_P1") (pintype "bidirectional"))
      (node (ref "U1") (pin "P18") (pinfunction "IO_L40N_7VREF_7_P18") (pintype "bidirectional"))
    )
    (net (code "84") (name "Net-(U$1-A12)") (class "Default")
      (node (ref "U$1") (pin "P12") (pinfunction "A12_P12") (pintype "bidirectional"))
      (node (ref "U1") (pin "P31") (pinfunction "IO_L21N_6_P31") (pintype "bidirectional"))
    )
    (net (code "85") (name "Net-(U$1-A13)") (class "Default")
      (node (ref "U$1") (pin "P4") (pinfunction "A13_P4") (pintype "bidirectional"))
      (node (ref "U1") (pin "P23") (pinfunction "IO_L24P_6_P23") (pintype "bidirectional"))
    )
    (net (code "86") (name "Net-(U$1-A14)") (class "Default")
      (node (ref "U$1") (pin "P11") (pinfunction "A14_P11") (pintype "bidirectional"))
      (node (ref "U1") (pin "P30") (pinfunction "IO_L21P_6_P30") (pintype "bidirectional"))
    )
    (net (code "87") (name "Net-(U$1-A15)") (class "Default")
      (node (ref "U$1") (pin "P7") (pinfunction "A15_P7") (pintype "bidirectional"))
      (node (ref "U1") (pin "P26") (pinfunction "IO_L23N_6_P26") (pintype "bidirectional"))
    )
    (net (code "88") (name "Net-(U$1-A16)") (class "Default")
      (node (ref "U$1") (pin "P10") (pinfunction "A16_P10") (pintype "bidirectional"))
      (node (ref "U1") (pin "P28") (pinfunction "IO_L22N_6_P28") (pintype "bidirectional"))
    )
    (net (code "89") (name "Net-(U$1-A17)") (class "Default")
      (node (ref "U$1") (pin "P6") (pinfunction "A17_P6") (pintype "bidirectional"))
      (node (ref "U1") (pin "P25") (pinfunction "IO_L23P_6_P25") (pintype "bidirectional"))
    )
    (net (code "90") (name "Net-(U$1-A18)") (class "Default")
      (node (ref "U$1") (pin "P9") (pinfunction "A18_P9") (pintype "bidirectional"))
      (node (ref "U1") (pin "P27") (pinfunction "IO_L22P_6_P27") (pintype "bidirectional"))
    )
    (net (code "91") (name "Net-(U$1-DQ0)") (class "Default")
      (node (ref "U$1") (pin "P21") (pinfunction "DQ0_P21") (pintype "bidirectional"))
      (node (ref "U1") (pin "P6") (pinfunction "IO_L20N_7_P6") (pintype "bidirectional"))
    )
    (net (code "92") (name "Net-(U$1-DQ1)") (class "Default")
      (node (ref "U$1") (pin "P22") (pinfunction "DQ1_P22") (pintype "bidirectional"))
      (node (ref "U1") (pin "P7") (pinfunction "IO_L21P_7_P7") (pintype "bidirectional"))
    )
    (net (code "93") (name "Net-(U$1-DQ2)") (class "Default")
      (node (ref "U$1") (pin "P23") (pinfunction "DQ2_P23") (pintype "bidirectional"))
      (node (ref "U1") (pin "P8") (pinfunction "IO_L21N_7_P8") (pintype "bidirectional"))
    )
    (net (code "94") (name "Net-(U$1-DQ3)") (class "Default")
      (node (ref "U$1") (pin "P25") (pinfunction "DQ3_P25") (pintype "bidirectional"))
      (node (ref "U1") (pin "P10") (pinfunction "IO_L22P_7_P10") (pintype "bidirectional"))
    )
    (net (code "95") (name "Net-(U$1-DQ4)") (class "Default")
      (node (ref "U$1") (pin "P26") (pinfunction "DQ4_P26") (pintype "bidirectional"))
      (node (ref "U1") (pin "P11") (pinfunction "IO_L22N_7_P11") (pintype "bidirectional"))
    )
    (net (code "96") (name "Net-(U$1-DQ5)") (class "Default")
      (node (ref "U$1") (pin "P27") (pinfunction "DQ5_P27") (pintype "bidirectional"))
      (node (ref "U1") (pin "P12") (pinfunction "IO_L23P_7_P12") (pintype "bidirectional"))
    )
    (net (code "97") (name "Net-(U$1-DQ6)") (class "Default")
      (node (ref "U$1") (pin "P28") (pinfunction "DQ6_P28") (pintype "bidirectional"))
      (node (ref "U1") (pin "P13") (pinfunction "IO_L23N_7_P13") (pintype "bidirectional"))
    )
    (net (code "98") (name "Net-(U$1-DQ7)") (class "Default")
      (node (ref "U$1") (pin "P29") (pinfunction "DQ7_P29") (pintype "bidirectional"))
      (node (ref "U1") (pin "P14") (pinfunction "IO_L24P_7_P14") (pintype "bidirectional"))
    )
    (net (code "99") (name "Net-(U$1-OE)") (class "Default")
      (node (ref "U$1") (pin "P32") (pinfunction "OE_P32") (pintype "bidirectional"))
      (node (ref "U1") (pin "P17") (pinfunction "IO_L40P_7_P17") (pintype "bidirectional"))
    )
    (net (code "100") (name "Net-(U$1-WE)") (class "Default")
      (node (ref "U$1") (pin "P5") (pinfunction "WE_P5") (pintype "bidirectional"))
      (node (ref "U1") (pin "P24") (pinfunction "IO_L24N_6VREF_6_P24") (pintype "bidirectional"))
    )
    (net (code "101") (name "Net-(U1I-IO_L32P_5GCLK2)") (class "Default")
      (node (ref "U$2") (pin "OUT") (pinfunction "OUT_OUT") (pintype "output"))
      (node (ref "U1") (pin "P52") (pinfunction "IO_L32P_5GCLK2_P52") (pintype "bidirectional"))
    )
    (net (code "102") (name "Net-(U1N-TCK)") (class "Default")
      (node (ref "R2") (pin "1") (pinfunction "1_1") (pintype "passive"))
      (node (ref "U1") (pin "P110") (pinfunction "TCK_P110") (pintype "bidirectional"))
    )
    (net (code "103") (name "Net-(U1N-TDI)") (class "Default")
      (node (ref "R1") (pin "1") (pinfunction "1_1") (pintype "passive"))
      (node (ref "U1") (pin "P144") (pinfunction "TDI_P144") (pintype "bidirectional"))
    )
    (net (code "104") (name "Net-(U1N-TMS)") (class "Default")
      (node (ref "R3") (pin "1") (pinfunction "1_1") (pintype "passive"))
      (node (ref "U1") (pin "P111") (pinfunction "TMS_P111") (pintype "bidirectional"))
    )
    (net (code "105") (name "Net-(X4A-F)") (class "Default")
      (node (ref "R40") (pin "2") (pinfunction "2_2") (pintype "passive"))
      (node (ref "X4") (pin "1") (pinfunction "F_1") (pintype "passive"))
    )
    (net (code "106") (name "Net-(X4B-F)") (class "Default")
      (node (ref "R41") (pin "2") (pinfunction "2_2") (pintype "passive"))
      (node (ref "X4") (pin "2") (pinfunction "F_2") (pintype "passive"))
    )
    (net (code "107") (name "Net-(X4C-F)") (class "Default")
      (node (ref "R42") (pin "2") (pinfunction "2_2") (pintype "passive"))
      (node (ref "X4") (pin "3") (pinfunction "F_3") (pintype "passive"))
    )
    (net (code "108") (name "Net-(X4D-F)") (class "Default")
      (node (ref "R43") (pin "2") (pinfunction "2_2") (pintype "passive"))
      (node (ref "X4") (pin "4") (pinfunction "F_4") (pintype "passive"))
    )
    (net (code "109") (name "Net-(X4F-F)") (class "Default")
      (node (ref "R44") (pin "2") (pinfunction "2_2") (pintype "passive"))
      (node (ref "X4") (pin "6") (pinfunction "F_6") (pintype "passive"))
    )
    (net (code "110") (name "Net-(X4G-F)") (class "Default")
      (node (ref "R45") (pin "2") (pinfunction "2_2") (pintype "passive"))
      (node (ref "X4") (pin "7") (pinfunction "F_7") (pintype "passive"))
    )
    (net (code "111") (name "Net-(X5A-F)") (class "Default")
      (node (ref "R46") (pin "1") (pinfunction "1_1") (pintype "passive"))
      (node (ref "X5") (pin "1") (pinfunction "F_1") (pintype "passive"))
    )
    (net (code "112") (name "Net-(X5B-F)") (class "Default")
      (node (ref "R39") (pin "1") (pinfunction "1_1") (pintype "passive"))
      (node (ref "X5") (pin "2") (pinfunction "F_2") (pintype "passive"))
    )
    (net (code "113") (name "Net-(X5C-F)") (class "Default")
      (node (ref "R38") (pin "1") (pinfunction "1_1") (pintype "passive"))
      (node (ref "X5") (pin "3") (pinfunction "F_3") (pintype "passive"))
    )
    (net (code "114") (name "Net-(X5D-F)") (class "Default")
      (node (ref "R37") (pin "1") (pinfunction "1_1") (pintype "passive"))
      (node (ref "X5") (pin "4") (pinfunction "F_4") (pintype "passive"))
    )
    (net (code "115") (name "Net-(X5F-F)") (class "Default")
      (node (ref "R36") (pin "1") (pinfunction "1_1") (pintype "passive"))
      (node (ref "X5") (pin "6") (pinfunction "F_6") (pintype "passive"))
    )
    (net (code "116") (name "Net-(X5G-F)") (class "Default")
      (node (ref "R35") (pin "1") (pinfunction "1_1") (pintype "passive"))
      (node (ref "X5") (pin "7") (pinfunction "F_7") (pintype "passive"))
    )
    (net (code "117") (name "unconnected-(IC1-NC.1-Pad2)") (class "Default")
      (node (ref "IC1") (pin "2") (pinfunction "NC.1_2") (pintype "bidirectional"))
    )
    (net (code "118") (name "unconnected-(IC1-NC.2-Pad9)") (class "Default")
      (node (ref "IC1") (pin "9") (pinfunction "NC.2_9") (pintype "bidirectional"))
    )
    (net (code "119") (name "unconnected-(IC1-NC.3-Pad12)") (class "Default")
      (node (ref "IC1") (pin "12") (pinfunction "NC.3_12") (pintype "bidirectional"))
    )
    (net (code "120") (name "unconnected-(IC1-NC.4-Pad14)") (class "Default")
      (node (ref "IC1") (pin "14") (pinfunction "NC.4_14") (pintype "bidirectional"))
    )
    (net (code "121") (name "unconnected-(IC1-NC.5-Pad15)") (class "Default")
      (node (ref "IC1") (pin "15") (pinfunction "NC.5_15") (pintype "bidirectional"))
    )
    (net (code "122") (name "unconnected-(IC1-NC.6-Pad16)") (class "Default")
      (node (ref "IC1") (pin "16") (pinfunction "NC.6_16") (pintype "bidirectional"))
    )
    (net (code "123") (name "unconnected-(IC1-{slash}CEO-Pad13)") (class "Default")
      (node (ref "IC1") (pin "13") (pinfunction "/CEO_13") (pintype "bidirectional"))
    )
    (net (code "124") (name "unconnected-(REG1.2-VOUT2-Pad2)") (class "Default")
      (node (ref "REG1.2") (pin "2") (pinfunction "VOUT2_2") (pintype "bidirectional"))
    )
    (net (code "125") (name "unconnected-(U$2-TRI-PadENA)") (class "Default")
      (node (ref "U$2") (pin "ENA") (pinfunction "TRI_ENA") (pintype "input"))
    )
    (net (code "126") (name "unconnected-(U1A-IO_L27P_0-PadP135)") (class "Default")
      (node (ref "U1") (pin "P135") (pinfunction "IO_L27P_0_P135") (pintype "bidirectional"))
    )
    (net (code "127") (name "unconnected-(U1A-IO_L30N_0-PadP132)") (class "Default")
      (node (ref "U1") (pin "P132") (pinfunction "IO_L30N_0_P132") (pintype "bidirectional"))
    )
    (net (code "128") (name "unconnected-(U1A-IO_L30P_0-PadP131)") (class "Default")
      (node (ref "U1") (pin "P131") (pinfunction "IO_L30P_0_P131") (pintype "bidirectional"))
    )
    (net (code "129") (name "unconnected-(U1A-IO_L31N_0-PadP130)") (class "Default")
      (node (ref "U1") (pin "P130") (pinfunction "IO_L31N_0_P130") (pintype "bidirectional"))
    )
    (net (code "130") (name "unconnected-(U1A-IO_L31P_0VREF_0-PadP129)") (class "Default")
      (node (ref "U1") (pin "P129") (pinfunction "IO_L31P_0VREF_0_P129") (pintype "bidirectional"))
    )
    (net (code "131") (name "unconnected-(U1A-IO_L32N_0GCLK7-PadP128)") (class "Default")
      (node (ref "U1") (pin "P128") (pinfunction "IO_L32N_0GCLK7_P128") (pintype "bidirectional"))
    )
    (net (code "132") (name "unconnected-(U1A-IO_L32P_0GCLK6-PadP127)") (class "Default")
      (node (ref "U1") (pin "P127") (pinfunction "IO_L32P_0GCLK6_P127") (pintype "bidirectional"))
    )
    (net (code "133") (name "unconnected-(U1C-IO-PadP116)") (class "Default")
      (node (ref "U1") (pin "P116") (pinfunction "IO_P116") (pintype "bidirectional"))
    )
    (net (code "134") (name "unconnected-(U1C-IO_L01N_1VRP_1-PadP113)") (class "Default")
      (node (ref "U1") (pin "P113") (pinfunction "IO_L01N_1VRP_1_P113") (pintype "bidirectional"))
    )
    (net (code "135") (name "unconnected-(U1C-IO_L01P_1VRN_1-PadP112)") (class "Default")
      (node (ref "U1") (pin "P112") (pinfunction "IO_L01P_1VRN_1_P112") (pintype "bidirectional"))
    )
    (net (code "136") (name "unconnected-(U1C-IO_L28N_1-PadP119)") (class "Default")
      (node (ref "U1") (pin "P119") (pinfunction "IO_L28N_1_P119") (pintype "bidirectional"))
    )
    (net (code "137") (name "unconnected-(U1C-IO_L28P_1-PadP118)") (class "Default")
      (node (ref "U1") (pin "P118") (pinfunction "IO_L28P_1_P118") (pintype "bidirectional"))
    )
    (net (code "138") (name "unconnected-(U1C-IO_L31N_1VREF_1-PadP123)") (class "Default")
      (node (ref "U1") (pin "P123") (pinfunction "IO_L31N_1VREF_1_P123") (pintype "bidirectional"))
    )
    (net (code "139") (name "unconnected-(U1C-IO_L31P_1-PadP122)") (class "Default")
      (node (ref "U1") (pin "P122") (pinfunction "IO_L31P_1_P122") (pintype "bidirectional"))
    )
    (net (code "140") (name "unconnected-(U1C-IO_L32N_1GCLK5-PadP125)") (class "Default")
      (node (ref "U1") (pin "P125") (pinfunction "IO_L32N_1GCLK5_P125") (pintype "bidirectional"))
    )
    (net (code "141") (name "unconnected-(U1C-IO_L32P_1GCLK4-PadP124)") (class "Default")
      (node (ref "U1") (pin "P124") (pinfunction "IO_L32P_1GCLK4_P124") (pintype "bidirectional"))
    )
    (net (code "142") (name "unconnected-(U1D-IO_L01N_2VRP_2-PadP108)") (class "Default")
      (node (ref "U1") (pin "P108") (pinfunction "IO_L01N_2VRP_2_P108") (pintype "bidirectional"))
    )
    (net (code "143") (name "unconnected-(U1D-IO_L01P_2VRN_2-PadP107)") (class "Default")
      (node (ref "U1") (pin "P107") (pinfunction "IO_L01P_2VRN_2_P107") (pintype "bidirectional"))
    )
    (net (code "144") (name "unconnected-(U1D-IO_L20N_2-PadP105)") (class "Default")
      (node (ref "U1") (pin "P105") (pinfunction "IO_L20N_2_P105") (pintype "bidirectional"))
    )
    (net (code "145") (name "unconnected-(U1D-IO_L20P_2-PadP104)") (class "Default")
      (node (ref "U1") (pin "P104") (pinfunction "IO_L20P_2_P104") (pintype "bidirectional"))
    )
    (net (code "146") (name "unconnected-(U1D-IO_L21N_2-PadP103)") (class "Default")
      (node (ref "U1") (pin "P103") (pinfunction "IO_L21N_2_P103") (pintype "bidirectional"))
    )
    (net (code "147") (name "unconnected-(U1D-IO_L21P_2-PadP102)") (class "Default")
      (node (ref "U1") (pin "P102") (pinfunction "IO_L21P_2_P102") (pintype "bidirectional"))
    )
    (net (code "148") (name "unconnected-(U1D-IO_L22N_2-PadP100)") (class "Default")
      (node (ref "U1") (pin "P100") (pinfunction "IO_L22N_2_P100") (pintype "bidirectional"))
    )
    (net (code "149") (name "unconnected-(U1D-IO_L22P_2-PadP99)") (class "Default")
      (node (ref "U1") (pin "P99") (pinfunction "IO_L22P_2_P99") (pintype "bidirectional"))
    )
    (net (code "150") (name "unconnected-(U1D-IO_L23N_2VREF_2-PadP98)") (class "Default")
      (node (ref "U1") (pin "P98") (pinfunction "IO_L23N_2VREF_2_P98") (pintype "bidirectional"))
    )
    (net (code "151") (name "unconnected-(U1D-IO_L23P_2-PadP97)") (class "Default")
      (node (ref "U1") (pin "P97") (pinfunction "IO_L23P_2_P97") (pintype "bidirectional"))
    )
    (net (code "152") (name "unconnected-(U1D-IO_L24N_2-PadP96)") (class "Default")
      (node (ref "U1") (pin "P96") (pinfunction "IO_L24N_2_P96") (pintype "bidirectional"))
    )
    (net (code "153") (name "unconnected-(U1D-IO_L24P_2-PadP95)") (class "Default")
      (node (ref "U1") (pin "P95") (pinfunction "IO_L24P_2_P95") (pintype "bidirectional"))
    )
    (net (code "154") (name "unconnected-(U1D-IO_L40N_2-PadP93)") (class "Default")
      (node (ref "U1") (pin "P93") (pinfunction "IO_L40N_2_P93") (pintype "bidirectional"))
    )
    (net (code "155") (name "unconnected-(U1D-IO_L40P_2VREF_2-PadP92)") (class "Default")
      (node (ref "U1") (pin "P92") (pinfunction "IO_L40P_2VREF_2_P92") (pintype "bidirectional"))
    )
    (net (code "156") (name "unconnected-(U1F-IO-PadP76)") (class "Default")
      (node (ref "U1") (pin "P76") (pinfunction "IO_P76") (pintype "bidirectional"))
    )
    (net (code "157") (name "unconnected-(U1F-IO_L01N_3VRP_3-PadP74)") (class "Default")
      (node (ref "U1") (pin "P74") (pinfunction "IO_L01N_3VRP_3_P74") (pintype "bidirectional"))
    )
    (net (code "158") (name "unconnected-(U1F-IO_L01P_3VRN_3-PadP73)") (class "Default")
      (node (ref "U1") (pin "P73") (pinfunction "IO_L01P_3VRN_3_P73") (pintype "bidirectional"))
    )
    (net (code "159") (name "unconnected-(U1F-IO_L20N_3-PadP78)") (class "Default")
      (node (ref "U1") (pin "P78") (pinfunction "IO_L20N_3_P78") (pintype "bidirectional"))
    )
    (net (code "160") (name "unconnected-(U1F-IO_L20P_3-PadP77)") (class "Default")
      (node (ref "U1") (pin "P77") (pinfunction "IO_L20P_3_P77") (pintype "bidirectional"))
    )
    (net (code "161") (name "unconnected-(U1F-IO_L21N_3-PadP80)") (class "Default")
      (node (ref "U1") (pin "P80") (pinfunction "IO_L21N_3_P80") (pintype "bidirectional"))
    )
    (net (code "162") (name "unconnected-(U1F-IO_L21P_3-PadP79)") (class "Default")
      (node (ref "U1") (pin "P79") (pinfunction "IO_L21P_3_P79") (pintype "bidirectional"))
    )
    (net (code "163") (name "unconnected-(U1F-IO_L22N_3-PadP83)") (class "Default")
      (node (ref "U1") (pin "P83") (pinfunction "IO_L22N_3_P83") (pintype "bidirectional"))
    )
    (net (code "164") (name "unconnected-(U1F-IO_L22P_3-PadP82)") (class "Default")
      (node (ref "U1") (pin "P82") (pinfunction "IO_L22P_3_P82") (pintype "bidirectional"))
    )
    (net (code "165") (name "unconnected-(U1F-IO_L23N_3-PadP85)") (class "Default")
      (node (ref "U1") (pin "P85") (pinfunction "IO_L23N_3_P85") (pintype "bidirectional"))
    )
    (net (code "166") (name "unconnected-(U1F-IO_L23P_3VREF_3-PadP84)") (class "Default")
      (node (ref "U1") (pin "P84") (pinfunction "IO_L23P_3VREF_3_P84") (pintype "bidirectional"))
    )
    (net (code "167") (name "unconnected-(U1F-IO_L24N_3-PadP87)") (class "Default")
      (node (ref "U1") (pin "P87") (pinfunction "IO_L24N_3_P87") (pintype "bidirectional"))
    )
    (net (code "168") (name "unconnected-(U1F-IO_L24P_3-PadP86)") (class "Default")
      (node (ref "U1") (pin "P86") (pinfunction "IO_L24P_3_P86") (pintype "bidirectional"))
    )
    (net (code "169") (name "unconnected-(U1F-IO_L40N_3VREF_3-PadP90)") (class "Default")
      (node (ref "U1") (pin "P90") (pinfunction "IO_L40N_3VREF_3_P90") (pintype "bidirectional"))
    )
    (net (code "170") (name "unconnected-(U1F-IO_L40P_3-PadP89)") (class "Default")
      (node (ref "U1") (pin "P89") (pinfunction "IO_L40P_3_P89") (pintype "bidirectional"))
    )
    (net (code "171") (name "unconnected-(U1G-IOVREF_4-PadP70)") (class "Default")
      (node (ref "U1") (pin "P70") (pinfunction "IOVREF_4_P70") (pintype "bidirectional"))
    )
    (net (code "172") (name "unconnected-(U1G-IO_L01N_4VRP_4-PadP69)") (class "Default")
      (node (ref "U1") (pin "P69") (pinfunction "IO_L01N_4VRP_4_P69") (pintype "bidirectional"))
    )
    (net (code "173") (name "unconnected-(U1G-IO_L01P_4VRN_4-PadP68)") (class "Default")
      (node (ref "U1") (pin "P68") (pinfunction "IO_L01P_4VRN_4_P68") (pintype "bidirectional"))
    )
    (net (code "174") (name "unconnected-(U1G-IO_L27P_4D1-PadP63)") (class "Default")
      (node (ref "U1") (pin "P63") (pinfunction "IO_L27P_4D1_P63") (pintype "bidirectional"))
    )
    (net (code "175") (name "unconnected-(U1G-IO_L30N_4D2-PadP60)") (class "Default")
      (node (ref "U1") (pin "P60") (pinfunction "IO_L30N_4D2_P60") (pintype "bidirectional"))
    )
    (net (code "176") (name "unconnected-(U1G-IO_L30P_4D3-PadP59)") (class "Default")
      (node (ref "U1") (pin "P59") (pinfunction "IO_L30P_4D3_P59") (pintype "bidirectional"))
    )
    (net (code "177") (name "unconnected-(U1G-IO_L31P_4DOUTBUSY-PadP57)") (class "Default")
      (node (ref "U1") (pin "P57") (pinfunction "IO_L31P_4DOUTBUSY_P57") (pintype "bidirectional"))
    )
    (net (code "178") (name "unconnected-(U1G-IO_L32N_4GCLK1-PadP56)") (class "Default")
      (node (ref "U1") (pin "P56") (pinfunction "IO_L32N_4GCLK1_P56") (pintype "bidirectional"))
    )
    (net (code "179") (name "unconnected-(U1G-IO_L32P_4GCLK0-PadP55)") (class "Default")
      (node (ref "U1") (pin "P55") (pinfunction "IO_L32P_4GCLK0_P55") (pintype "bidirectional"))
    )
    (net (code "180") (name "unconnected-(U1I-IO_L32N_5GCLK3-PadP53)") (class "Default")
      (node (ref "U1") (pin "P53") (pinfunction "IO_L32N_5GCLK3_P53") (pintype "bidirectional"))
    )
    (net (code "181") (name "unconnected-(U1N-HSWAP_EN-PadP142)") (class "Default")
      (node (ref "U1") (pin "P142") (pinfunction "HSWAP_EN_P142") (pintype "bidirectional"))
    )
    (net (code "182") (name "unconnected-(X1-3-Pad2)") (class "Default")
      (node (ref "X1") (pin "2") (pinfunction "3_2") (pintype "passive"))
    )
    (net (code "183") (name "unconnected-(X2-Pad10)") (class "Default")
      (node (ref "X2") (pin "10") (pinfunction "10_10") (pintype "passive"))
    )
    (net (code "184") (name "unconnected-(X2-Pad12)") (class "Default")
      (node (ref "X2") (pin "12") (pinfunction "12_12") (pintype "passive"))
    )
    (net (code "185") (name "unconnected-(X3-Pad2)") (class "Default")
      (node (ref "X3") (pin "2") (pinfunction "2_2") (pintype "passive"))
    )
    (net (code "186") (name "unconnected-(X3-Pad8)") (class "Default")
      (node (ref "X3") (pin "8") (pinfunction "8_8") (pintype "passive"))
    )
    (net (code "187") (name "unconnected-(X4-PadG2)") (class "Default")
      (node (ref "X4") (pin "G2") (pinfunction "G2_G2") (pintype "passive"))
    )
    (net (code "188") (name "unconnected-(X5-PadG2)") (class "Default")
      (node (ref "X5") (pin "G2") (pinfunction "G2_G2") (pintype "passive"))
    )
  )
)
